# Port.net
KiCad netlist of a schematic drawn in Altium Designer
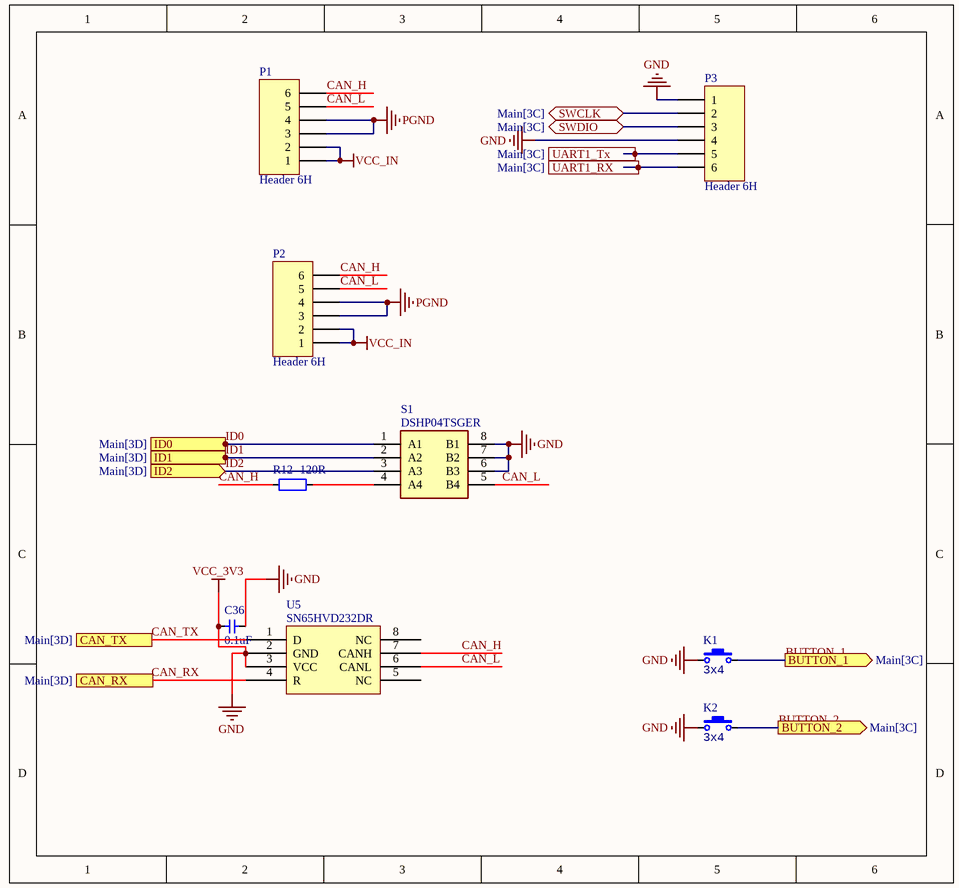
[diagram p0: Port.SchDoc]

(export (version "E")
  (design (tool "Eeschema 10.0.6"))
  (components
    (comp (ref "C36")
      (value "0.1uF")
      (footprint "motor42-lib:CAP_0402")
      (description "Capacitor")
      (libsource (lib "MyPcbLib") (part "电容-0402"))
    )
    (comp (ref "K1")
      (value "3x4")
      (footprint "ButtonTACT_3x4x2_180")
      (description "Button")
      (fields (field (name "Comment") "TACT 2P"))
      (libsource (lib "KitSprout") (part "ButtonTACT_3x4x2_180"))
    )
    (comp (ref "K2")
      (value "3x4")
      (footprint "ButtonTACT_3x4x2_180")
      (description "Button")
      (fields (field (name "Comment") "TACT 2P"))
      (libsource (lib "KitSprout") (part "ButtonTACT_3x4x2_180"))
    )
    (comp (ref "P1")
      (value "Header 6H")
      (footprint "CONN-TH_HC-ZH1.5-6A-s")
      (description "Header, 6-Pin, Right Angle")
      (fields (field (name "PUBLISHER") "Altium Limited"))
      (libsource (lib "Miscellaneous Connectors") (part "Header 6H"))
    )
    (comp (ref "P2")
      (value "Header 6H")
      (footprint "CONN-TH_HC-ZH1.5-6A-s")
      (description "Header, 6-Pin, Right Angle")
      (fields (field (name "PUBLISHER") "Altium Limited"))
      (libsource (lib "Miscellaneous Connectors") (part "Header 6H"))
    )
    (comp (ref "P3")
      (value "Header 6H")
      (footprint "CONN-TH_HC-ZH1.5-6A-s")
      (description "Header, 6-Pin, Right Angle")
      (fields (field (name "PUBLISHER") "Altium Limited"))
      (libsource (lib "") (part "Header 6H_1"))
    )
    (comp (ref "R12")
      (value "120R")
      (footprint "RES_0402")
      (description "Resistor")
      (libsource (lib "MyPcbLib") (part "电阻-0402"))
    )
    (comp (ref "S1")
      (value "DSHP04TSGER")
      (footprint "SW-SMD_DSHP04TS-S")
      (description "DIP Switches / SIP Switches 4 pos. low profile Btm Seal Tape J Bend")
      (fields
        (field (name "MOUSER PART NUMBER") "774-218-4LPSTJ")
        (field (name "MANUFACTURER_PART_NUMBER") "218-4LPSTJ")
      )
      (libsource (lib "Schlib1") (part "218-4LPSTJ"))
    )
    (comp (ref "U5")
      (value "SN65HVD232D")
      (footprint "so-8")
      (fields
        (field (name "MANUFACTURER") "Texas Instruments")
        (field (name "MANUFACTURER PART NUMBER") "SN65HVD232DR")
      )
      (libsource (lib "MyPcbLib") (part "SN65HVD232D"))
    )
  )
  (nets
    (net (code "1") (name "/BUTTON_1") (class "Default")
      (node (ref "K1") (pin "2") (pinfunction "2_2") (pintype "passive"))
    )
    (net (code "2") (name "/BUTTON_2") (class "Default")
      (node (ref "K2") (pin "2") (pinfunction "2_2") (pintype "passive"))
    )
    (net (code "3") (name "/CAN_H") (class "Default")
      (node (ref "P1") (pin "6") (pinfunction "6_6") (pintype "passive"))
      (node (ref "P2") (pin "6") (pinfunction "6_6") (pintype "passive"))
      (node (ref "R12") (pin "1") (pinfunction "1_1") (pintype "passive"))
      (node (ref "U5") (pin "7") (pinfunction "CANH_7") (pintype "passive"))
    )
    (net (code "4") (name "/CAN_L") (class "Default")
      (node (ref "P1") (pin "5") (pinfunction "5_5") (pintype "passive"))
      (node (ref "P2") (pin "5") (pinfunction "5_5") (pintype "passive"))
      (node (ref "S1") (pin "5") (pinfunction "B4_5") (pintype "passive"))
      (node (ref "U5") (pin "6") (pinfunction "CANL_6") (pintype "passive"))
    )
    (net (code "5") (name "/CAN_RX") (class "Default")
      (node (ref "U5") (pin "4") (pinfunction "R_4") (pintype "passive"))
    )
    (net (code "6") (name "/CAN_TX") (class "Default")
      (node (ref "U5") (pin "1") (pinfunction "D_1") (pintype "passive"))
    )
    (net (code "7") (name "/ID0") (class "Default")
      (node (ref "S1") (pin "1") (pinfunction "A1_1") (pintype "passive"))
    )
    (net (code "8") (name "/ID1") (class "Default")
      (node (ref "S1") (pin "2") (pinfunction "A2_2") (pintype "passive"))
    )
    (net (code "9") (name "/ID2") (class "Default")
      (node (ref "S1") (pin "3") (pinfunction "A3_3") (pintype "passive"))
    )
    (net (code "10") (name "/SWCLK") (class "Default")
      (node (ref "P3") (pin "2") (pinfunction "2_2") (pintype "passive"))
    )
    (net (code "11") (name "/SWDIO") (class "Default")
      (node (ref "P3") (pin "3") (pinfunction "3_3") (pintype "passive"))
    )
    (net (code "12") (name "/UART1_RX") (class "Default")
      (node (ref "P3") (pin "6") (pinfunction "6_6") (pintype "passive"))
    )
    (net (code "13") (name "/UART1_Tx") (class "Default")
      (node (ref "P3") (pin "5") (pinfunction "5_5") (pintype "passive"))
    )
    (net (code "14") (name "GND") (class "Default")
      (node (ref "C36") (pin "1") (pinfunction "1_1") (pintype "passive"))
      (node (ref "C36") (pin "2") (pinfunction "2_2") (pintype "passive"))
      (node (ref "K1") (pin "1") (pinfunction "1_1") (pintype "passive"))
      (node (ref "K2") (pin "1") (pinfunction "1_1") (pintype "passive"))
      (node (ref "P3") (pin "1") (pinfunction "1_1") (pintype "passive"))
      (node (ref "P3") (pin "4") (pinfunction "4_4") (pintype "passive"))
      (node (ref "S1") (pin "6") (pinfunction "B3_6") (pintype "passive"))
      (node (ref "S1") (pin "7") (pinfunction "B2_7") (pintype "passive"))
      (node (ref "S1") (pin "8") (pinfunction "B1_8") (pintype "passive"))
      (node (ref "U5") (pin "2") (pinfunction "GND_2") (pintype "passive"))
      (node (ref "U5") (pin "3") (pinfunction "VCC_3") (pintype "passive"))
    )
    (net (code "15") (name "Net-(S1-A4)") (class "Default")
      (node (ref "R12") (pin "2") (pinfunction "2_2") (pintype "passive"))
      (node (ref "S1") (pin "4") (pinfunction "A4_4") (pintype "passive"))
    )
    (net (code "16") (name "PGND") (class "Default")
      (node (ref "P1") (pin "3") (pinfunction "3_3") (pintype "passive"))
      (node (ref "P1") (pin "4") (pinfunction "4_4") (pintype "passive"))
      (node (ref "P2") (pin "3") (pinfunction "3_3") (pintype "passive"))
      (node (ref "P2") (pin "4") (pinfunction "4_4") (pintype "passive"))
    )
    (net (code "17") (name "VCC_IN") (class "Default")
      (node (ref "P1") (pin "1") (pinfunction "1_1") (pintype "passive"))
      (node (ref "P1") (pin "2") (pinfunction "2_2") (pintype "passive"))
      (node (ref "P2") (pin "1") (pinfunction "1_1") (pintype "passive"))
      (node (ref "P2") (pin "2") (pinfunction "2_2") (pintype "passive"))
    )
    (net (code "18") (name "unconnected-(U5-NC-Pad5)") (class "Default")
      (node (ref "U5") (pin "5") (pinfunction "NC_5") (pintype "passive"))
    )
    (net (code "19") (name "unconnected-(U5-NC-Pad8)") (class "Default")
      (node (ref "U5") (pin "8") (pinfunction "NC_8") (pintype "passive"))
    )
  )
)
